# 1_CORE_schdoc.net
KiCad netlist of a schematic drawn in Altium Designer
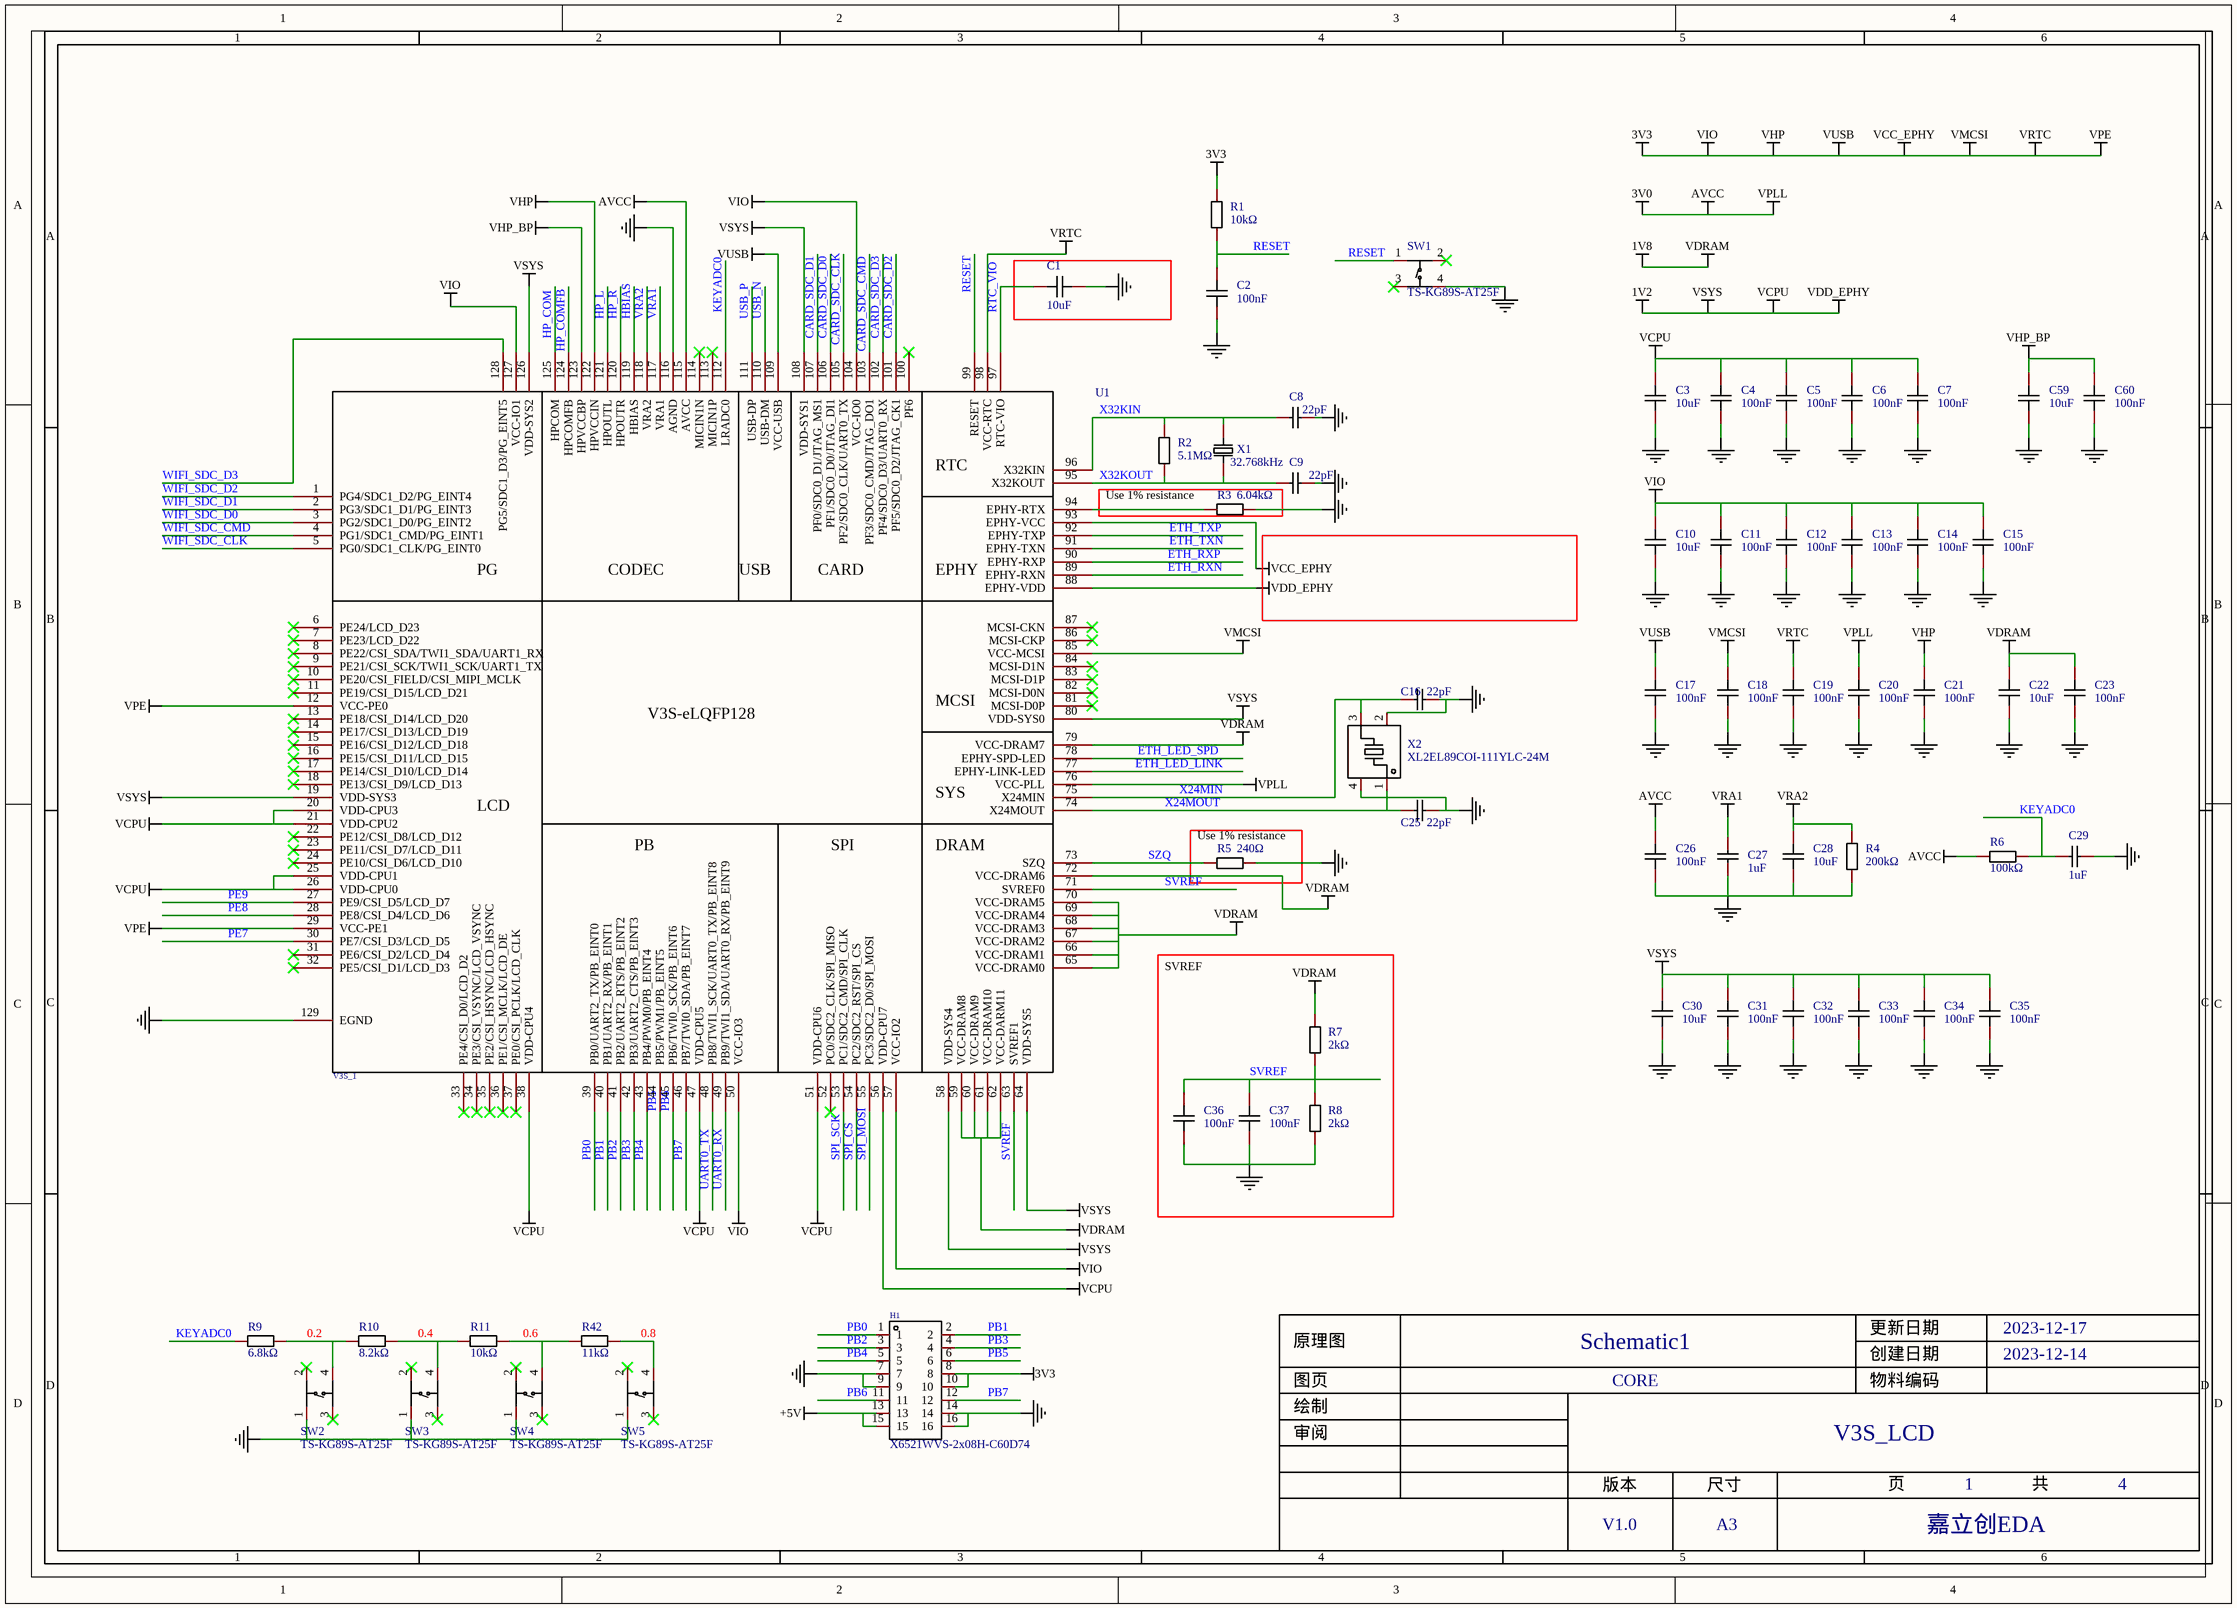
[diagram p0: 1_CORE.schdoc.schdoc]

(export (version "E")
  (design (tool "Eeschema 10.0.6"))
  (components
    (comp (ref "C1")
      (value "10uF")
      (fields
        (field (name "NAME") "10uF")
        (field (name "MANUFACTURER") "SAMSUNG(三星)")
        (field (name "MANUFACTURER PART") "CL10A106KP8NNNC")
        (field (name "TOLERANCE") "±10%")
      )
      (libsource (lib "altium-import") (part "root_0_CL10A106KP8NNNC_"))
    )
    (comp (ref "C2")
      (value "100nF")
      (fields
        (field (name "NAME") "100nF")
        (field (name "MANUFACTURER") "YAGEO(国巨)")
        (field (name "MANUFACTURER PART") "CC0603KRX7R9BB104")
        (field (name "TOLERANCE") "±10%")
      )
      (libsource (lib "altium-import") (part "root_1_CC0603KRX7R9BB104_"))
    )
    (comp (ref "C3")
      (value "10uF")
      (fields
        (field (name "NAME") "10uF")
        (field (name "MANUFACTURER") "SAMSUNG(三星)")
        (field (name "MANUFACTURER PART") "CL10A106KP8NNNC")
        (field (name "TOLERANCE") "±10%")
      )
      (libsource (lib "altium-import") (part "root_1_CL10A106KP8NNNC_"))
    )
    (comp (ref "C4")
      (value "100nF")
      (fields
        (field (name "NAME") "100nF")
        (field (name "MANUFACTURER") "YAGEO(国巨)")
        (field (name "MANUFACTURER PART") "CC0603KRX7R9BB104")
        (field (name "TOLERANCE") "±10%")
      )
      (libsource (lib "altium-import") (part "root_1_CC0603KRX7R9BB104_"))
    )
    (comp (ref "C5")
      (value "100nF")
      (fields
        (field (name "NAME") "100nF")
        (field (name "MANUFACTURER") "YAGEO(国巨)")
        (field (name "MANUFACTURER PART") "CC0603KRX7R9BB104")
        (field (name "TOLERANCE") "±10%")
      )
      (libsource (lib "altium-import") (part "root_1_CC0603KRX7R9BB104_"))
    )
    (comp (ref "C6")
      (value "100nF")
      (fields
        (field (name "NAME") "100nF")
        (field (name "MANUFACTURER") "YAGEO(国巨)")
        (field (name "MANUFACTURER PART") "CC0603KRX7R9BB104")
        (field (name "TOLERANCE") "±10%")
      )
      (libsource (lib "altium-import") (part "root_1_CC0603KRX7R9BB104_"))
    )
    (comp (ref "C7")
      (value "100nF")
      (fields
        (field (name "NAME") "100nF")
        (field (name "MANUFACTURER") "YAGEO(国巨)")
        (field (name "MANUFACTURER PART") "CC0603KRX7R9BB104")
        (field (name "TOLERANCE") "±10%")
      )
      (libsource (lib "altium-import") (part "root_1_CC0603KRX7R9BB104_"))
    )
    (comp (ref "C8")
      (value "22pF")
      (fields
        (field (name "NAME") "22pF")
        (field (name "MANUFACTURER PART") "CL10C220JB8NNNC")
        (field (name "MANUFACTURER") "SAMSUNG(三星)")
        (field (name "TOLERANCE") "±5%")
      )
      (libsource (lib "altium-import") (part "root_2_CL10C220JB8NNNC_"))
    )
    (comp (ref "C9")
      (value "22pF")
      (fields
        (field (name "NAME") "22pF")
        (field (name "MANUFACTURER PART") "CL10C220JB8NNNC")
        (field (name "MANUFACTURER") "SAMSUNG(三星)")
        (field (name "TOLERANCE") "±5%")
      )
      (libsource (lib "altium-import") (part "root_2_CL10C220JB8NNNC_"))
    )
    (comp (ref "C10")
      (value "10uF")
      (fields
        (field (name "NAME") "10uF")
        (field (name "MANUFACTURER") "SAMSUNG(三星)")
        (field (name "MANUFACTURER PART") "CL10A106KP8NNNC")
        (field (name "TOLERANCE") "±10%")
      )
      (libsource (lib "altium-import") (part "root_1_CL10A106KP8NNNC_"))
    )
    (comp (ref "C11")
      (value "100nF")
      (fields
        (field (name "NAME") "100nF")
        (field (name "MANUFACTURER") "YAGEO(国巨)")
        (field (name "MANUFACTURER PART") "CC0603KRX7R9BB104")
        (field (name "TOLERANCE") "±10%")
      )
      (libsource (lib "altium-import") (part "root_1_CC0603KRX7R9BB104_"))
    )
    (comp (ref "C12")
      (value "100nF")
      (fields
        (field (name "NAME") "100nF")
        (field (name "MANUFACTURER") "YAGEO(国巨)")
        (field (name "MANUFACTURER PART") "CC0603KRX7R9BB104")
        (field (name "TOLERANCE") "±10%")
      )
      (libsource (lib "altium-import") (part "root_1_CC0603KRX7R9BB104_"))
    )
    (comp (ref "C13")
      (value "100nF")
      (fields
        (field (name "NAME") "100nF")
        (field (name "MANUFACTURER") "YAGEO(国巨)")
        (field (name "MANUFACTURER PART") "CC0603KRX7R9BB104")
        (field (name "TOLERANCE") "±10%")
      )
      (libsource (lib "altium-import") (part "root_1_CC0603KRX7R9BB104_"))
    )
    (comp (ref "C14")
      (value "100nF")
      (fields
        (field (name "NAME") "100nF")
        (field (name "MANUFACTURER") "YAGEO(国巨)")
        (field (name "MANUFACTURER PART") "CC0603KRX7R9BB104")
        (field (name "TOLERANCE") "±10%")
      )
      (libsource (lib "altium-import") (part "root_1_CC0603KRX7R9BB104_"))
    )
    (comp (ref "C15")
      (value "100nF")
      (fields
        (field (name "NAME") "100nF")
        (field (name "MANUFACTURER") "YAGEO(国巨)")
        (field (name "MANUFACTURER PART") "CC0603KRX7R9BB104")
        (field (name "TOLERANCE") "±10%")
      )
      (libsource (lib "altium-import") (part "root_1_CC0603KRX7R9BB104_"))
    )
    (comp (ref "C16")
      (value "22pF")
      (fields
        (field (name "NAME") "22pF")
        (field (name "MANUFACTURER PART") "CL10C220JB8NNNC")
        (field (name "MANUFACTURER") "SAMSUNG(三星)")
        (field (name "TOLERANCE") "±5%")
      )
      (libsource (lib "altium-import") (part "root_0_CL10C220JB8NNNC_"))
    )
    (comp (ref "C17")
      (value "100nF")
      (fields
        (field (name "NAME") "100nF")
        (field (name "MANUFACTURER") "YAGEO(国巨)")
        (field (name "MANUFACTURER PART") "CC0603KRX7R9BB104")
        (field (name "TOLERANCE") "±10%")
      )
      (libsource (lib "altium-import") (part "root_1_CC0603KRX7R9BB104_"))
    )
    (comp (ref "C18")
      (value "100nF")
      (fields
        (field (name "NAME") "100nF")
        (field (name "MANUFACTURER") "YAGEO(国巨)")
        (field (name "MANUFACTURER PART") "CC0603KRX7R9BB104")
        (field (name "TOLERANCE") "±10%")
      )
      (libsource (lib "altium-import") (part "root_1_CC0603KRX7R9BB104_"))
    )
    (comp (ref "C19")
      (value "100nF")
      (fields
        (field (name "NAME") "100nF")
        (field (name "MANUFACTURER") "YAGEO(国巨)")
        (field (name "MANUFACTURER PART") "CC0603KRX7R9BB104")
        (field (name "TOLERANCE") "±10%")
      )
      (libsource (lib "altium-import") (part "root_1_CC0603KRX7R9BB104_"))
    )
    (comp (ref "C20")
      (value "100nF")
      (fields
        (field (name "NAME") "100nF")
        (field (name "MANUFACTURER") "YAGEO(国巨)")
        (field (name "MANUFACTURER PART") "CC0603KRX7R9BB104")
        (field (name "TOLERANCE") "±10%")
      )
      (libsource (lib "altium-import") (part "root_1_CC0603KRX7R9BB104_"))
    )
    (comp (ref "C21")
      (value "100nF")
      (fields
        (field (name "NAME") "100nF")
        (field (name "MANUFACTURER") "YAGEO(国巨)")
        (field (name "MANUFACTURER PART") "CC0603KRX7R9BB104")
        (field (name "TOLERANCE") "±10%")
      )
      (libsource (lib "altium-import") (part "root_1_CC0603KRX7R9BB104_"))
    )
    (comp (ref "C22")
      (value "10uF")
      (fields
        (field (name "NAME") "10uF")
        (field (name "MANUFACTURER") "SAMSUNG(三星)")
        (field (name "MANUFACTURER PART") "CL10A106KP8NNNC")
        (field (name "TOLERANCE") "±10%")
      )
      (libsource (lib "altium-import") (part "root_1_CL10A106KP8NNNC_"))
    )
    (comp (ref "C23")
      (value "100nF")
      (fields
        (field (name "NAME") "100nF")
        (field (name "MANUFACTURER") "YAGEO(国巨)")
        (field (name "MANUFACTURER PART") "CC0603KRX7R9BB104")
        (field (name "TOLERANCE") "±10%")
      )
      (libsource (lib "altium-import") (part "root_1_CC0603KRX7R9BB104_"))
    )
    (comp (ref "C25")
      (value "22pF")
      (fields
        (field (name "NAME") "22pF")
        (field (name "MANUFACTURER PART") "CL10C220JB8NNNC")
        (field (name "MANUFACTURER") "SAMSUNG(三星)")
        (field (name "TOLERANCE") "±5%")
      )
      (libsource (lib "altium-import") (part "root_0_CL10C220JB8NNNC_"))
    )
    (comp (ref "C26")
      (value "100nF")
      (fields
        (field (name "NAME") "100nF")
        (field (name "MANUFACTURER") "YAGEO(国巨)")
        (field (name "MANUFACTURER PART") "CC0603KRX7R9BB104")
        (field (name "TOLERANCE") "±10%")
      )
      (libsource (lib "altium-import") (part "root_1_CC0603KRX7R9BB104_"))
    )
    (comp (ref "C27")
      (value "1uF")
      (fields
        (field (name "NAME") "1uF")
        (field (name "MANUFACTURER PART") "CL10A105KB8NNNC")
        (field (name "MANUFACTURER") "SAMSUNG(三星)")
        (field (name "TOLERANCE") "±10%")
      )
      (libsource (lib "altium-import") (part "root_1_CL10A105KB8NNNC_"))
    )
    (comp (ref "C28")
      (value "10uF")
      (fields
        (field (name "NAME") "10uF")
        (field (name "MANUFACTURER") "SAMSUNG(三星)")
        (field (name "MANUFACTURER PART") "CL10A106KP8NNNC")
        (field (name "TOLERANCE") "±10%")
      )
      (libsource (lib "altium-import") (part "root_1_CL10A106KP8NNNC_"))
    )
    (comp (ref "C29")
      (value "1uF")
      (fields
        (field (name "NAME") "1uF")
        (field (name "MANUFACTURER PART") "CL10A105KB8NNNC")
        (field (name "MANUFACTURER") "SAMSUNG(三星)")
        (field (name "TOLERANCE") "±10%")
      )
      (libsource (lib "altium-import") (part "root_0_CL10A105KB8NNNC_"))
    )
    (comp (ref "C30")
      (value "10uF")
      (fields
        (field (name "NAME") "10uF")
        (field (name "MANUFACTURER") "SAMSUNG(三星)")
        (field (name "MANUFACTURER PART") "CL10A106KP8NNNC")
        (field (name "TOLERANCE") "±10%")
      )
      (libsource (lib "altium-import") (part "root_1_CL10A106KP8NNNC_"))
    )
    (comp (ref "C31")
      (value "100nF")
      (fields
        (field (name "NAME") "100nF")
        (field (name "MANUFACTURER") "YAGEO(国巨)")
        (field (name "MANUFACTURER PART") "CC0603KRX7R9BB104")
        (field (name "TOLERANCE") "±10%")
      )
      (libsource (lib "altium-import") (part "root_1_CC0603KRX7R9BB104_"))
    )
    (comp (ref "C32")
      (value "100nF")
      (fields
        (field (name "NAME") "100nF")
        (field (name "MANUFACTURER") "YAGEO(国巨)")
        (field (name "MANUFACTURER PART") "CC0603KRX7R9BB104")
        (field (name "TOLERANCE") "±10%")
      )
      (libsource (lib "altium-import") (part "root_1_CC0603KRX7R9BB104_"))
    )
    (comp (ref "C33")
      (value "100nF")
      (fields
        (field (name "NAME") "100nF")
        (field (name "MANUFACTURER") "YAGEO(国巨)")
        (field (name "MANUFACTURER PART") "CC0603KRX7R9BB104")
        (field (name "TOLERANCE") "±10%")
      )
      (libsource (lib "altium-import") (part "root_1_CC0603KRX7R9BB104_"))
    )
    (comp (ref "C34")
      (value "100nF")
      (fields
        (field (name "NAME") "100nF")
        (field (name "MANUFACTURER") "YAGEO(国巨)")
        (field (name "MANUFACTURER PART") "CC0603KRX7R9BB104")
        (field (name "TOLERANCE") "±10%")
      )
      (libsource (lib "altium-import") (part "root_1_CC0603KRX7R9BB104_"))
    )
    (comp (ref "C35")
      (value "100nF")
      (fields
        (field (name "NAME") "100nF")
        (field (name "MANUFACTURER") "YAGEO(国巨)")
        (field (name "MANUFACTURER PART") "CC0603KRX7R9BB104")
        (field (name "TOLERANCE") "±10%")
      )
      (libsource (lib "altium-import") (part "root_1_CC0603KRX7R9BB104_"))
    )
    (comp (ref "C36")
      (value "100nF")
      (fields
        (field (name "NAME") "100nF")
        (field (name "MANUFACTURER") "YAGEO(国巨)")
        (field (name "MANUFACTURER PART") "CC0603KRX7R9BB104")
        (field (name "TOLERANCE") "±10%")
      )
      (libsource (lib "altium-import") (part "root_1_CC0603KRX7R9BB104_"))
    )
    (comp (ref "C37")
      (value "100nF")
      (fields
        (field (name "NAME") "100nF")
        (field (name "MANUFACTURER") "YAGEO(国巨)")
        (field (name "MANUFACTURER PART") "CC0603KRX7R9BB104")
        (field (name "TOLERANCE") "±10%")
      )
      (libsource (lib "altium-import") (part "root_1_CC0603KRX7R9BB104_"))
    )
    (comp (ref "C59")
      (value "10uF")
      (fields
        (field (name "NAME") "10uF")
        (field (name "MANUFACTURER") "SAMSUNG(三星)")
        (field (name "MANUFACTURER PART") "CL10A106KP8NNNC")
        (field (name "TOLERANCE") "±10%")
      )
      (libsource (lib "altium-import") (part "root_1_CL10A106KP8NNNC_"))
    )
    (comp (ref "C60")
      (value "100nF")
      (fields
        (field (name "NAME") "100nF")
        (field (name "MANUFACTURER") "YAGEO(国巨)")
        (field (name "MANUFACTURER PART") "CC0603KRX7R9BB104")
        (field (name "TOLERANCE") "±10%")
      )
      (libsource (lib "altium-import") (part "root_1_CC0603KRX7R9BB104_"))
    )
    (comp (ref "H1")
      (value "X6521WVS-2x08H-C60D74")
      (fields
        (field (name "NAME") "X6521WVS-2x08H-C60D74")
        (field (name "MANUFACTURER") "XKB Connectivity(中国星坤)")
      )
      (libsource (lib "altium-import") (part "root_0_X6521WVS-2x08H-C60D74_"))
    )
    (comp (ref "R1")
      (value "10kΩ")
      (fields
        (field (name "NAME") "10kΩ")
        (field (name "MANUFACTURER") "UNI-ROYAL(厚声)")
        (field (name "MANUFACTURER PART") "0603WAF1002T5E")
        (field (name "TOLERANCE") "±1%")
      )
      (libsource (lib "altium-import") (part "root_1_0603WAF1002T5E_"))
    )
    (comp (ref "R2")
      (value "5.1MΩ")
      (fields
        (field (name "NAME") "5.1MΩ")
        (field (name "MANUFACTURER") "UNI-ROYAL(厚声)")
        (field (name "MANUFACTURER PART") "0603WAF5104T5E")
        (field (name "TOLERANCE") "±1%")
      )
      (libsource (lib "altium-import") (part "root_1_0603WAF5104T5E_"))
    )
    (comp (ref "R3")
      (value "6.04kΩ")
      (fields
        (field (name "NAME") "6.04kΩ")
        (field (name "MANUFACTURER") "FH(风华)")
        (field (name "MANUFACTURER PART") "RS-03K6041FT")
        (field (name "TOLERANCE") "±1%")
      )
      (libsource (lib "altium-import") (part "root_0_RS-03K6041FT_"))
    )
    (comp (ref "R4")
      (value "200kΩ")
      (fields
        (field (name "NAME") "200kΩ")
        (field (name "MANUFACTURER") "UNI-ROYAL(厚声)")
        (field (name "MANUFACTURER PART") "0603WAF2003T5E")
        (field (name "TOLERANCE") "±1%")
      )
      (libsource (lib "altium-import") (part "root_1_0603WAF2003T5E_"))
    )
    (comp (ref "R5")
      (value "240Ω")
      (fields
        (field (name "NAME") "240Ω")
        (field (name "MANUFACTURER") "UNI-ROYAL(厚声)")
        (field (name "MANUFACTURER PART") "0603WAF2400T5E")
        (field (name "TOLERANCE") "±1%")
      )
      (libsource (lib "altium-import") (part "root_0_0603WAF2400T5E_"))
    )
    (comp (ref "R6")
      (value "100kΩ")
      (fields
        (field (name "NAME") "100kΩ")
        (field (name "MANUFACTURER") "UNI-ROYAL(厚声)")
        (field (name "MANUFACTURER PART") "0603WAF1003T5E")
        (field (name "TOLERANCE") "±1%")
      )
      (libsource (lib "altium-import") (part "root_0_0603WAF1003T5E_"))
    )
    (comp (ref "R7")
      (value "2kΩ")
      (fields
        (field (name "NAME") "2kΩ")
        (field (name "MANUFACTURER") "UNI-ROYAL(厚声)")
        (field (name "MANUFACTURER PART") "0603WAF2001T5E")
        (field (name "TOLERANCE") "±1%")
      )
      (libsource (lib "altium-import") (part "root_1_0603WAF2001T5E_"))
    )
    (comp (ref "R8")
      (value "2kΩ")
      (fields
        (field (name "NAME") "2kΩ")
        (field (name "MANUFACTURER") "UNI-ROYAL(厚声)")
        (field (name "MANUFACTURER PART") "0603WAF2001T5E")
        (field (name "TOLERANCE") "±1%")
      )
      (libsource (lib "altium-import") (part "root_1_0603WAF2001T5E_"))
    )
    (comp (ref "R9")
      (value "6.8kΩ")
      (fields
        (field (name "NAME") "6.8kΩ")
        (field (name "MANUFACTURER") "UNI-ROYAL(厚声)")
        (field (name "MANUFACTURER PART") "0603WAF6801T5E")
        (field (name "TOLERANCE") "±1%")
      )
      (libsource (lib "altium-import") (part "root_0_0603WAF6801T5E_"))
    )
    (comp (ref "R10")
      (value "8.2kΩ")
      (fields
        (field (name "NAME") "8.2kΩ")
        (field (name "MANUFACTURER") "UNI-ROYAL(厚声)")
        (field (name "MANUFACTURER PART") "0603WAF8201T5E")
        (field (name "TOLERANCE") "±1%")
      )
      (libsource (lib "altium-import") (part "root_0_0603WAF8201T5E_"))
    )
    (comp (ref "R11")
      (value "10kΩ")
      (fields
        (field (name "NAME") "10kΩ")
        (field (name "MANUFACTURER") "UNI-ROYAL(厚声)")
        (field (name "MANUFACTURER PART") "0603WAF1002T5E")
        (field (name "TOLERANCE") "±1%")
      )
      (libsource (lib "altium-import") (part "root_0_0603WAF1002T5E_"))
    )
    (comp (ref "R42")
      (value "11kΩ")
      (fields
        (field (name "NAME") "11kΩ")
        (field (name "MANUFACTURER") "UNI-ROYAL(厚声)")
        (field (name "MANUFACTURER PART") "0603WAF1102T5E")
        (field (name "TOLERANCE") "±1%")
      )
      (libsource (lib "altium-import") (part "root_0_0603WAF1102T5E_"))
    )
    (comp (ref "SW1")
      (value "TS-KG89S-AT25F")
      (description "触点电流:50mA;额定电压(DC):12V;绝缘电阻:100MΩ;电路结构:单刀单掷;安装方式:立贴;作用力:250gf@±50gf;机械寿命:10万次;带支架:否;")
      (fields (field (name "NAME") "TS-KG89S-AT25F") (field (name "MANUFACTURER") "HANBO(汉博)"))
      (libsource (lib "altium-import") (part "root_0_TS-KG89S-AT25F_"))
    )
    (comp (ref "SW2")
      (value "TS-KG89S-AT25F")
      (description "触点电流:50mA;额定电压(DC):12V;绝缘电阻:100MΩ;电路结构:单刀单掷;安装方式:立贴;作用力:250gf@±50gf;机械寿命:10万次;带支架:否;")
      (fields (field (name "NAME") "TS-KG89S-AT25F") (field (name "MANUFACTURER") "HANBO(汉博)"))
      (libsource (lib "altium-import") (part "root_1_TS-KG89S-AT25F_"))
    )
    (comp (ref "SW3")
      (value "TS-KG89S-AT25F")
      (description "触点电流:50mA;额定电压(DC):12V;绝缘电阻:100MΩ;电路结构:单刀单掷;安装方式:立贴;作用力:250gf@±50gf;机械寿命:10万次;带支架:否;")
      (fields (field (name "NAME") "TS-KG89S-AT25F") (field (name "MANUFACTURER") "HANBO(汉博)"))
      (libsource (lib "altium-import") (part "root_1_TS-KG89S-AT25F_"))
    )
    (comp (ref "SW4")
      (value "TS-KG89S-AT25F")
      (description "触点电流:50mA;额定电压(DC):12V;绝缘电阻:100MΩ;电路结构:单刀单掷;安装方式:立贴;作用力:250gf@±50gf;机械寿命:10万次;带支架:否;")
      (fields (field (name "NAME") "TS-KG89S-AT25F") (field (name "MANUFACTURER") "HANBO(汉博)"))
      (libsource (lib "altium-import") (part "root_1_TS-KG89S-AT25F_"))
    )
    (comp (ref "SW5")
      (value "TS-KG89S-AT25F")
      (description "触点电流:50mA;额定电压(DC):12V;绝缘电阻:100MΩ;电路结构:单刀单掷;安装方式:立贴;作用力:250gf@±50gf;机械寿命:10万次;带支架:否;")
      (fields (field (name "NAME") "TS-KG89S-AT25F") (field (name "MANUFACTURER") "HANBO(汉博)"))
      (libsource (lib "altium-import") (part "root_1_TS-KG89S-AT25F_"))
    )
    (comp (ref "U1")
      (value "V3S_1")
      (fields (field (name "NAME") "V3S_1"))
      (libsource (lib "altium-import") (part "root_0_LQFP129 14x14_N_"))
    )
    (comp (ref "X1")
      (value "32.768kHz")
      (description "频率:32.768kHz;负载电容:12.5pF;频率公差:±20ppm;")
      (fields
        (field (name "NAME") "32.768kHz")
        (field (name "MANUFACTURER PART") "Q13FC1350000400")
        (field (name "MANUFACTURER") "EPSON(爱普生)")
      )
      (libsource (lib "altium-import") (part "root_1_Q13FC1350000400_"))
    )
    (comp (ref "X2")
      (value "XL2EL89COI-111YLC-24M")
      (description "频率： 24MHZ 负载： 12PF 频率公差： ±10PPM 工作温度： -40~85℃")
      (fields (field (name "NAME") "XL2EL89COI-111YLC-24M") (field (name "MANUFACTURER") "YXC(扬兴晶振)"))
      (libsource (lib "altium-import") (part "root_1_XL2EL89COI-111YLC-24M_"))
    )
  )
  (nets
    (net (code "1") (name "+5V") (class "Default")
      (node (ref "H1") (pin "13") (pinfunction "13_13") (pintype "passive"))
      (node (ref "H1") (pin "15") (pinfunction "15_15") (pintype "passive"))
    )
    (net (code "2") (name "/CARD_SDC_CLK") (class "Default")
      (node (ref "U1") (pin "105") (pinfunction "PF2/SDC0_CLK/UART0_TX_105") (pintype "passive"))
    )
    (net (code "3") (name "/CARD_SDC_CMD") (class "Default")
      (node (ref "U1") (pin "103") (pinfunction "PF3/SDC0_CMD/JTAG_DO1_103") (pintype "passive"))
    )
    (net (code "4") (name "/CARD_SDC_D0") (class "Default")
      (node (ref "U1") (pin "106") (pinfunction "PF1/SDC0_D0/JTAG_DI1_106") (pintype "passive"))
    )
    (net (code "5") (name "/CARD_SDC_D1") (class "Default")
      (node (ref "U1") (pin "107") (pinfunction "PF0/SDC0_D1/JTAG_MS1_107") (pintype "passive"))
    )
    (net (code "6") (name "/CARD_SDC_D2") (class "Default")
      (node (ref "U1") (pin "101") (pinfunction "PF5/SDC0_D2/JTAG_CK1_101") (pintype "passive"))
    )
    (net (code "7") (name "/CARD_SDC_D3") (class "Default")
      (node (ref "U1") (pin "102") (pinfunction "PF4/SDC0_D3/UART0_RX_102") (pintype "passive"))
    )
    (net (code "8") (name "/ETH_LED_LINK") (class "Default")
      (node (ref "U1") (pin "77") (pinfunction "EPHY-LINK-LED_77") (pintype "passive"))
    )
    (net (code "9") (name "/ETH_LED_SPD") (class "Default")
      (node (ref "U1") (pin "78") (pinfunction "EPHY-SPD-LED_78") (pintype "passive"))
    )
    (net (code "10") (name "/ETH_RXN") (class "Default")
      (node (ref "U1") (pin "89") (pinfunction "EPHY-RXN_89") (pintype "passive"))
    )
    (net (code "11") (name "/ETH_RXP") (class "Default")
      (node (ref "U1") (pin "90") (pinfunction "EPHY-RXP_90") (pintype "passive"))
    )
    (net (code "12") (name "/ETH_TXN") (class "Default")
      (node (ref "U1") (pin "91") (pinfunction "EPHY-TXN_91") (pintype "passive"))
    )
    (net (code "13") (name "/ETH_TXP") (class "Default")
      (node (ref "U1") (pin "92") (pinfunction "EPHY-TXP_92") (pintype "passive"))
    )
    (net (code "14") (name "/HBIAS") (class "Default")
      (node (ref "U1") (pin "119") (pinfunction "HBIAS_119") (pintype "passive"))
    )
    (net (code "15") (name "/HP_COM") (class "Default")
      (node (ref "U1") (pin "125") (pinfunction "HPCOM_125") (pintype "passive"))
    )
    (net (code "16") (name "/HP_COMFB") (class "Default")
      (node (ref "U1") (pin "124") (pinfunction "HPCOMFB_124") (pintype "passive"))
    )
    (net (code "17") (name "/HP_L") (class "Default")
      (node (ref "U1") (pin "121") (pinfunction "HPOUTL_121") (pintype "passive"))
    )
    (net (code "18") (name "/HP_R") (class "Default")
      (node (ref "U1") (pin "120") (pinfunction "HPOUTR_120") (pintype "passive"))
    )
    (net (code "19") (name "/KEYADC0") (class "Default")
      (node (ref "C29") (pin "1") (pinfunction "1_1") (pintype "passive"))
      (node (ref "R6") (pin "2") (pinfunction "2_2") (pintype "passive"))
      (node (ref "R9") (pin "1") (pinfunction "1_1") (pintype "passive"))
      (node (ref "U1") (pin "112") (pinfunction "LRADC0_112") (pintype "passive"))
    )
    (net (code "20") (name "/PB0") (class "Default")
      (node (ref "H1") (pin "1") (pinfunction "1_1") (pintype "passive"))
      (node (ref "U1") (pin "39") (pinfunction "PB0/UART2_TX/PB_EINT0_39") (pintype "passive"))
    )
    (net (code "21") (name "/PB1") (class "Default")
      (node (ref "H1") (pin "2") (pinfunction "2_2") (pintype "passive"))
      (node (ref "U1") (pin "40") (pinfunction "PB1/UART2_RX/PB_EINT1_40") (pintype "passive"))
    )
    (net (code "22") (name "/PB2") (class "Default")
      (node (ref "H1") (pin "3") (pinfunction "3_3") (pintype "passive"))
      (node (ref "U1") (pin "41") (pinfunction "PB2/UART2_RTS/PB_EINT2_41") (pintype "passive"))
    )
    (net (code "23") (name "/PB3") (class "Default")
      (node (ref "H1") (pin "4") (pinfunction "4_4") (pintype "passive"))
      (node (ref "U1") (pin "42") (pinfunction "PB3/UART2_CTS/PB_EINT3_42") (pintype "passive"))
    )
    (net (code "24") (name "/PB4") (class "Default")
      (node (ref "H1") (pin "5") (pinfunction "5_5") (pintype "passive"))
      (node (ref "U1") (pin "43") (pinfunction "PB4/PWM0/PB_EINT4_43") (pintype "passive"))
    )
    (net (code "25") (name "/PB5") (class "Default")
      (node (ref "H1") (pin "6") (pinfunction "6_6") (pintype "passive"))
      (node (ref "U1") (pin "44") (pinfunction "PB5/PWM1/PB_EINT5_44") (pintype "passive"))
    )
    (net (code "26") (name "/PB6") (class "Default")
      (node (ref "H1") (pin "11") (pinfunction "11_11") (pintype "passive"))
      (node (ref "U1") (pin "45") (pinfunction "PB6/TWI0_SCK/PB_EINT6_45") (pintype "passive"))
    )
    (net (code "27") (name "/PB7") (class "Default")
      (node (ref "H1") (pin "12") (pinfunction "12_12") (pintype "passive"))
      (node (ref "U1") (pin "46") (pinfunction "PB7/TWI0_SDA/PB_EINT7_46") (pintype "passive"))
    )
    (net (code "28") (name "/PE7") (class "Default")
      (node (ref "U1") (pin "30") (pinfunction "PE7/CSI_D3/LCD_D5_30") (pintype "passive"))
    )
    (net (code "29") (name "/PE8") (class "Default")
      (node (ref "U1") (pin "28") (pinfunction "PE8/CSI_D4/LCD_D6_28") (pintype "passive"))
    )
    (net (code "30") (name "/PE9") (class "Default")
      (node (ref "U1") (pin "27") (pinfunction "PE9/CSI_D5/LCD_D7_27") (pintype "passive"))
    )
    (net (code "31") (name "/RESET") (class "Default")
      (node (ref "C2") (pin "2") (pinfunction "2_2") (pintype "passive"))
      (node (ref "R1") (pin "1") (pinfunction "1_1") (pintype "passive"))
      (node (ref "SW1") (pin "1") (pinfunction "1_1") (pintype "passive"))
      (node (ref "U1") (pin "99") (pinfunction "RESET_99") (pintype "passive"))
    )
    (net (code "32") (name "/RTC_VIO") (class "Default")
      (node (ref "C1") (pin "1") (pinfunction "1_1") (pintype "passive"))
      (node (ref "U1") (pin "97") (pinfunction "RTC-VIO_97") (pintype "passive"))
    )
    (net (code "33") (name "/SPI_CS") (class "Default")
      (node (ref "U1") (pin "54") (pinfunction "PC2/SDC2_RST/SPI_CS_54") (pintype "passive"))
    )
    (net (code "34") (name "/SPI_MOSI") (class "Default")
      (node (ref "U1") (pin "55") (pinfunction "PC3/SDC2_D0/SPI_MOSI_55") (pintype "passive"))
    )
    (net (code "35") (name "/SPI_SCK") (class "Default")
      (node (ref "U1") (pin "53") (pinfunction "PC1/SDC2_CMD/SPI_CLK_53") (pintype "passive"))
    )
    (net (code "36") (name "/SVREF") (class "Default")
      (node (ref "C36") (pin "2") (pinfunction "2_2") (pintype "passive"))
      (node (ref "C37") (pin "2") (pinfunction "2_2") (pintype "passive"))
      (node (ref "R7") (pin "1") (pinfunction "1_1") (pintype "passive"))
      (node (ref "R8") (pin "2") (pinfunction "2_2") (pintype "passive"))
      (node (ref "U1") (pin "63") (pinfunction "SVREF1_63") (pintype "passive"))
      (node (ref "U1") (pin "71") (pinfunction "SVREF0_71") (pintype "passive"))
    )
    (net (code "37") (name "/SZQ") (class "Default")
      (node (ref "R5") (pin "1") (pinfunction "1_1") (pintype "passive"))
      (node (ref "U1") (pin "73") (pinfunction "SZQ_73") (pintype "passive"))
    )
    (net (code "38") (name "/UART0_RX") (class "Default")
      (node (ref "U1") (pin "49") (pinfunction "PB9/TWI1_SDA/UART0_RX/PB_EINT9_49") (pintype "passive"))
    )
    (net (code "39") (name "/UART0_TX") (class "Default")
      (node (ref "U1") (pin "48") (pinfunction "PB8/TWI1_SCK/UART0_TX/PB_EINT8_48") (pintype "passive"))
    )
    (net (code "40") (name "/USB_N") (class "Default")
      (node (ref "U1") (pin "110") (pinfunction "USB-DM_110") (pintype "passive"))
    )
    (net (code "41") (name "/USB_P") (class "Default")
      (node (ref "U1") (pin "111") (pinfunction "USB-DP_111") (pintype "passive"))
    )
    (net (code "42") (name "/WIFI_SDC_CLK") (class "Default")
      (node (ref "U1") (pin "5") (pinfunction "PG0/SDC1_CLK/PG_EINT0_5") (pintype "passive"))
    )
    (net (code "43") (name "/WIFI_SDC_CMD") (class "Default")
      (node (ref "U1") (pin "4") (pinfunction "PG1/SDC1_CMD/PG_EINT1_4") (pintype "passive"))
    )
    (net (code "44") (name "/WIFI_SDC_D0") (class "Default")
      (node (ref "U1") (pin "3") (pinfunction "PG2/SDC1_D0/PG_EINT2_3") (pintype "passive"))
    )
    (net (code "45") (name "/WIFI_SDC_D1") (class "Default")
      (node (ref "U1") (pin "2") (pinfunction "PG3/SDC1_D1/PG_EINT3_2") (pintype "passive"))
    )
    (net (code "46") (name "/WIFI_SDC_D2") (class "Default")
      (node (ref "U1") (pin "1") (pinfunction "PG4/SDC1_D2/PG_EINT4_1") (pintype "passive"))
    )
    (net (code "47") (name "/WIFI_SDC_D3") (class "Default")
      (node (ref "U1") (pin "128") (pinfunction "PG5/SDC1_D3/PG_EINT5_128") (pintype "passive"))
    )
    (net (code "48") (name "/X24MIN") (class "Default")
      (node (ref "C16") (pin "1") (pinfunction "1_1") (pintype "passive"))
      (node (ref "U1") (pin "75") (pinfunction "X24MIN_75") (pintype "passive"))
      (node (ref "X2") (pin "3") (pinfunction "3_3") (pintype "passive"))
    )
    (net (code "49") (name "/X24MOUT") (class "Default")
      (node (ref "C25") (pin "1") (pinfunction "1_1") (pintype "passive"))
      (node (ref "U1") (pin "74") (pinfunction "X24MOUT_74") (pintype "passive"))
      (node (ref "X2") (pin "1") (pinfunction "1_1") (pintype "passive"))
    )
    (net (code "50") (name "/X32KIN") (class "Default")
      (node (ref "C8") (pin "2") (pinfunction "2_2") (pintype "passive"))
      (node (ref "R2") (pin "2") (pinfunction "2_2") (pintype "passive"))
      (node (ref "U1") (pin "96") (pinfunction "X32KIN_96") (pintype "passive"))
      (node (ref "X1") (pin "2") (pinfunction "2_2") (pintype "passive"))
    )
    (net (code "51") (name "/X32KOUT") (class "Default")
      (node (ref "C9") (pin "2") (pinfunction "2_2") (pintype "passive"))
      (node (ref "R2") (pin "1") (pinfunction "1_1") (pintype "passive"))
      (node (ref "U1") (pin "95") (pinfunction "X32KOUT_95") (pintype "passive"))
      (node (ref "X1") (pin "1") (pinfunction "1_1") (pintype "passive"))
    )
    (net (code "52") (name "1V2") (class "Default")
      (node (ref "C3") (pin "2") (pinfunction "2_2") (pintype "passive"))
      (node (ref "C30") (pin "2") (pinfunction "2_2") (pintype "passive"))
      (node (ref "C31") (pin "2") (pinfunction "2_2") (pintype "passive"))
      (node (ref "C32") (pin "2") (pinfunction "2_2") (pintype "passive"))
      (node (ref "C33") (pin "2") (pinfunction "2_2") (pintype "passive"))
      (node (ref "C34") (pin "2") (pinfunction "2_2") (pintype "passive"))
      (node (ref "C35") (pin "2") (pinfunction "2_2") (pintype "passive"))
      (node (ref "C4") (pin "2") (pinfunction "2_2") (pintype "passive"))
      (node (ref "C5") (pin "2") (pinfunction "2_2") (pintype "passive"))
      (node (ref "C6") (pin "2") (pinfunction "2_2") (pintype "passive"))
      (node (ref "C7") (pin "2") (pinfunction "2_2") (pintype "passive"))
      (node (ref "U1") (pin "108") (pinfunction "VDD-SYS1_108") (pintype "passive"))
      (node (ref "U1") (pin "126") (pinfunction "VDD-SYS2_126") (pintype "passive"))
      (node (ref "U1") (pin "19") (pinfunction "VDD-SYS3_19") (pintype "passive"))
      (node (ref "U1") (pin "20") (pinfunction "VDD-CPU3_20") (pintype "passive"))
      (node (ref "U1") (pin "21") (pinfunction "VDD-CPU2_21") (pintype "passive"))
      (node (ref "U1") (pin "25") (pinfunction "VDD-CPU1_25") (pintype "passive"))
      (node (ref "U1") (pin "26") (pinfunction "VDD-CPU0_26") (pintype "passive"))
      (node (ref "U1") (pin "38") (pinfunction "VDD-CPU4_38") (pintype "passive"))
      (node (ref "U1") (pin "47") (pinfunction "VDD-CPU5_47") (pintype "passive"))
      (node (ref "U1") (pin "51") (pinfunction "VDD-CPU6_51") (pintype "passive"))
      (node (ref "U1") (pin "56") (pinfunction "VDD-CPU7_56") (pintype "passive"))
      (node (ref "U1") (pin "58") (pinfunction "VDD-SYS4_58") (pintype "passive"))
      (node (ref "U1") (pin "64") (pinfunction "VDD-SYS5_64") (pintype "passive"))
      (node (ref "U1") (pin "80") (pinfunction "VDD-SYS0_80") (pintype "passive"))
      (node (ref "U1") (pin "88") (pinfunction "EPHY-VDD_88") (pintype "passive"))
    )
    (net (code "53") (name "1V8") (class "Default")
      (node (ref "C22") (pin "2") (pinfunction "2_2") (pintype "passive"))
      (node (ref "C23") (pin "2") (pinfunction "2_2") (pintype "passive"))
      (node (ref "R7") (pin "2") (pinfunction "2_2") (pintype "passive"))
      (node (ref "U1") (pin "59") (pinfunction "VCC-DRAM8_59") (pintype "passive"))
      (node (ref "U1") (pin "60") (pinfunction "VCC-DRAM9_60") (pintype "passive"))
      (node (ref "U1") (pin "61") (pinfunction "VCC-DRAM10_61") (pintype "passive"))
      (node (ref "U1") (pin "62") (pinfunction "VCC-DARM11_62") (pintype "passive"))
      (node (ref "U1") (pin "65") (pinfunction "VCC-DRAM0_65") (pintype "passive"))
      (node (ref "U1") (pin "66") (pinfunction "VCC-DRAM1_66") (pintype "passive"))
      (node (ref "U1") (pin "67") (pinfunction "VCC-DRAM2_67") (pintype "passive"))
      (node (ref "U1") (pin "68") (pinfunction "VCC-DRAM3_68") (pintype "passive"))
      (node (ref "U1") (pin "69") (pinfunction "VCC-DRAM4_69") (pintype "passive"))
      (node (ref "U1") (pin "70") (pinfunction "VCC-DRAM5_70") (pintype "passive"))
      (node (ref "U1") (pin "72") (pinfunction "VCC-DRAM6_72") (pintype "passive"))
      (node (ref "U1") (pin "79") (pinfunction "VCC-DRAM7_79") (pintype "passive"))
    )
    (net (code "54") (name "3V0") (class "Default")
      (node (ref "C20") (pin "2") (pinfunction "2_2") (pintype "passive"))
      (node (ref "C26") (pin "2") (pinfunction "2_2") (pintype "passive"))
      (node (ref "R6") (pin "1") (pinfunction "1_1") (pintype "passive"))
      (node (ref "U1") (pin "115") (pinfunction "AVCC_115") (pintype "passive"))
      (node (ref "U1") (pin "76") (pinfunction "VCC-PLL_76") (pintype "passive"))
    )
    (net (code "55") (name "3V3") (class "Default")
      (node (ref "C10") (pin "2") (pinfunction "2_2") (pintype "passive"))
      (node (ref "C11") (pin "2") (pinfunction "2_2") (pintype "passive"))
      (node (ref "C12") (pin "2") (pinfunction "2_2") (pintype "passive"))
      (node (ref "C13") (pin "2") (pinfunction "2_2") (pintype "passive"))
      (node (ref "C14") (pin "2") (pinfunction "2_2") (pintype "passive"))
      (node (ref "C15") (pin "2") (pinfunction "2_2") (pintype "passive"))
      (node (ref "C17") (pin "2") (pinfunction "2_2") (pintype "passive"))
      (node (ref "C18") (pin "2") (pinfunction "2_2") (pintype "passive"))
      (node (ref "C19") (pin "2") (pinfunction "2_2") (pintype "passive"))
      (node (ref "C21") (pin "2") (pinfunction "2_2") (pintype "passive"))
      (node (ref "H1") (pin "10") (pinfunction "10_10") (pintype "passive"))
      (node (ref "H1") (pin "8") (pinfunction "8_8") (pintype "passive"))
      (node (ref "R1") (pin "2") (pinfunction "2_2") (pintype "passive"))
      (node (ref "U1") (pin "104") (pinfunction "VCC-IO0_104") (pintype "passive"))
      (node (ref "U1") (pin "109") (pinfunction "VCC-USB_109") (pintype "passive"))
      (node (ref "U1") (pin "12") (pinfunction "VCC-PE0_12") (pintype "passive"))
      (node (ref "U1") (pin "122") (pinfunction "HPVCCIN_122") (pintype "passive"))
      (node (ref "U1") (pin "127") (pinfunction "VCC-IO1_127") (pintype "passive"))
      (node (ref "U1") (pin "29") (pinfunction "VCC-PE1_29") (pintype "passive"))
      (node (ref "U1") (pin "50") (pinfunction "VCC-IO3_50") (pintype "passive"))
      (node (ref "U1") (pin "57") (pinfunction "VCC-IO2_57") (pintype "passive"))
      (node (ref "U1") (pin "85") (pinfunction "VCC-MCSI_85") (pintype "passive"))
      (node (ref "U1") (pin "93") (pinfunction "EPHY-VCC_93") (pintype "passive"))
      (node (ref "U1") (pin "98") (pinfunction "VCC-RTC_98") (pintype "passive"))
    )
    (net (code "56") (name "<NO NET>") (class "Default")
      (node (ref "C1") (pin "2") (pinfunction "2_2") (pintype "passive"))
      (node (ref "C10") (pin "1") (pinfunction "1_1") (pintype "passive"))
      (node (ref "C11") (pin "1") (pinfunction "1_1") (pintype "passive"))
      (node (ref "C12") (pin "1") (pinfunction "1_1") (pintype "passive"))
      (node (ref "C13") (pin "1") (pinfunction "1_1") (pintype "passive"))
      (node (ref "C14") (pin "1") (pinfunction "1_1") (pintype "passive"))
      (node (ref "C15") (pin "1") (pinfunction "1_1") (pintype "passive"))
      (node (ref "C16") (pin "2") (pinfunction "2_2") (pintype "passive"))
      (node (ref "C17") (pin "1") (pinfunction "1_1") (pintype "passive"))
      (node (ref "C18") (pin "1") (pinfunction "1_1") (pintype "passive"))
      (node (ref "C19") (pin "1") (pinfunction "1_1") (pintype "passive"))
      (node (ref "C2") (pin "1") (pinfunction "1_1") (pintype "passive"))
      (node (ref "C20") (pin "1") (pinfunction "1_1") (pintype "passive"))
      (node (ref "C21") (pin "1") (pinfunction "1_1") (pintype "passive"))
      (node (ref "C22") (pin "1") (pinfunction "1_1") (pintype "passive"))
      (node (ref "C23") (pin "1") (pinfunction "1_1") (pintype "passive"))
      (node (ref "C25") (pin "2") (pinfunction "2_2") (pintype "passive"))
      (node (ref "C26") (pin "1") (pinfunction "1_1") (pintype "passive"))
      (node (ref "C27") (pin "1") (pinfunction "1_1") (pintype "passive"))
      (node (ref "C28") (pin "1") (pinfunction "1_1") (pintype "passive"))
      (node (ref "C29") (pin "2") (pinfunction "2_2") (pintype "passive"))
      (node (ref "C3") (pin "1") (pinfunction "1_1") (pintype "passive"))
      (node (ref "C30") (pin "1") (pinfunction "1_1") (pintype "passive"))
      (node (ref "C31") (pin "1") (pinfunction "1_1") (pintype "passive"))
      (node (ref "C32") (pin "1") (pinfunction "1_1") (pintype "passive"))
      (node (ref "C33") (pin "1") (pinfunction "1_1") (pintype "passive"))
      (node (ref "C34") (pin "1") (pinfunction "1_1") (pintype "passive"))
      (node (ref "C35") (pin "1") (pinfunction "1_1") (pintype "passive"))
      (node (ref "C36") (pin "1") (pinfunction "1_1") (pintype "passive"))
      (node (ref "C37") (pin "1") (pinfunction "1_1") (pintype "passive"))
      (node (ref "C4") (pin "1") (pinfunction "1_1") (pintype "passive"))
      (node (ref "C5") (pin "1") (pinfunction "1_1") (pintype "passive"))
      (node (ref "C59") (pin "1") (pinfunction "1_1") (pintype "passive"))
      (node (ref "C6") (pin "1") (pinfunction "1_1") (pintype "passive"))
      (node (ref "C60") (pin "1") (pinfunction "1_1") (pintype "passive"))
      (node (ref "C7") (pin "1") (pinfunction "1_1") (pintype "passive"))
      (node (ref "C8") (pin "1") (pinfunction "1_1") (pintype "passive"))
      (node (ref "C9") (pin "1") (pinfunction "1_1") (pintype "passive"))
      (node (ref "H1") (pin "14") (pinfunction "14_14") (pintype "passive"))
      (node (ref "H1") (pin "16") (pinfunction "16_16") (pintype "passive"))
      (node (ref "H1") (pin "7") (pinfunction "7_7") (pintype "passive"))
      (node (ref "H1") (pin "9") (pinfunction "9_9") (pintype "passive"))
      (node (ref "R3") (pin "2") (pinfunction "2_2") (pintype "passive"))
      (node (ref "R4") (pin "1") (pinfunction "1_1") (pintype "passive"))
      (node (ref "R5") (pin "2") (pinfunction "2_2") (pintype "passive"))
      (node (ref "R8") (pin "1") (pinfunction "1_1") (pintype "passive"))
      (node (ref "SW1") (pin "4") (pinfunction "4_4") (pintype "passive"))
      (node (ref "SW2") (pin "1") (pinfunction "1_1") (pintype "passive"))
      (node (ref "SW3") (pin "1") (pinfunction "1_1") (pintype "passive"))
      (node (ref "SW4") (pin "1") (pinfunction "1_1") (pintype "passive"))
      (node (ref "SW5") (pin "1") (pinfunction "1_1") (pintype "passive"))
      (node (ref "U1") (pin "116") (pinfunction "AGND_116") (pintype "passive"))
      (node (ref "U1") (pin "129") (pinfunction "EGND_129") (pintype "passive"))
      (node (ref "X2") (pin "2") (pinfunction "GND_2") (pintype "passive"))
      (node (ref "X2") (pin "4") (pinfunction "GND_4") (pintype "passive"))
    )
    (net (code "57") (name "Net-(R10-Pad1)") (class "Default")
      (node (ref "R10") (pin "1") (pinfunction "1_1") (pintype "passive"))
      (node (ref "R9") (pin "2") (pinfunction "2_2") (pintype "passive"))
      (node (ref "SW2") (pin "4") (pinfunction "4_4") (pintype "passive"))
    )
    (net (code "58") (name "Net-(R10-Pad2)") (class "Default")
      (node (ref "R10") (pin "2") (pinfunction "2_2") (pintype "passive"))
      (node (ref "R11") (pin "1") (pinfunction "1_1") (pintype "passive"))
      (node (ref "SW3") (pin "4") (pinfunction "4_4") (pintype "passive"))
    )
    (net (code "59") (name "Net-(R11-Pad2)") (class "Default")
      (node (ref "R11") (pin "2") (pinfunction "2_2") (pintype "passive"))
      (node (ref "R42") (pin "1") (pinfunction "1_1") (pintype "passive"))
      (node (ref "SW4") (pin "4") (pinfunction "4_4") (pintype "passive"))
    )
    (net (code "60") (name "Net-(R42-Pad2)") (class "Default")
      (node (ref "R42") (pin "2") (pinfunction "2_2") (pintype "passive"))
      (node (ref "SW5") (pin "4") (pinfunction "4_4") (pintype "passive"))
    )
    (net (code "61") (name "Net-(U1-EPHY-RTX)") (class "Default")
      (node (ref "R3") (pin "1") (pinfunction "1_1") (pintype "passive"))
      (node (ref "U1") (pin "94") (pinfunction "EPHY-RTX_94") (pintype "passive"))
    )
    (net (code "62") (name "VHP_BP") (class "Default")
      (node (ref "C59") (pin "2") (pinfunction "2_2") (pintype "passive"))
      (node (ref "C60") (pin "2") (pinfunction "2_2") (pintype "passive"))
      (node (ref "U1") (pin "123") (pinfunction "HPVCCBP_123") (pintype "passive"))
    )
    (net (code "63") (name "VRA1") (class "Default")
      (node (ref "C27") (pin "2") (pinfunction "2_2") (pintype "passive"))
      (node (ref "U1") (pin "117") (pinfunction "VRA1_117") (pintype "passive"))
    )
    (net (code "64") (name "VRA2") (class "Default")
      (node (ref "C28") (pin "2") (pinfunction "2_2") (pintype "passive"))
      (node (ref "R4") (pin "2") (pinfunction "2_2") (pintype "passive"))
      (node (ref "U1") (pin "118") (pinfunction "VRA2_118") (pintype "passive"))
    )
    (net (code "65") (name "unconnected-(SW1-Pad2)") (class "Default")
      (node (ref "SW1") (pin "2") (pinfunction "2_2") (pintype "passive+no_connect"))
    )
    (net (code "66") (name "unconnected-(SW1-Pad3)") (class "Default")
      (node (ref "SW1") (pin "3") (pinfunction "3_3") (pintype "passive+no_connect"))
    )
    (net (code "67") (name "unconnected-(SW2-Pad2)") (class "Default")
      (node (ref "SW2") (pin "2") (pinfunction "2_2") (pintype "passive+no_connect"))
    )
    (net (code "68") (name "unconnected-(SW2-Pad3)") (class "Default")
      (node (ref "SW2") (pin "3") (pinfunction "3_3") (pintype "passive+no_connect"))
    )
    (net (code "69") (name "unconnected-(SW3-Pad2)") (class "Default")
      (node (ref "SW3") (pin "2") (pinfunction "2_2") (pintype "passive+no_connect"))
    )
    (net (code "70") (name "unconnected-(SW3-Pad3)") (class "Default")
      (node (ref "SW3") (pin "3") (pinfunction "3_3") (pintype "passive+no_connect"))
    )
    (net (code "71") (name "unconnected-(SW4-Pad2)") (class "Default")
      (node (ref "SW4") (pin "2") (pinfunction "2_2") (pintype "passive+no_connect"))
    )
    (net (code "72") (name "unconnected-(SW4-Pad3)") (class "Default")
      (node (ref "SW4") (pin "3") (pinfunction "3_3") (pintype "passive+no_connect"))
    )
    (net (code "73") (name "unconnected-(SW5-Pad2)") (class "Default")
      (node (ref "SW5") (pin "2") (pinfunction "2_2") (pintype "passive+no_connect"))
    )
    (net (code "74") (name "unconnected-(SW5-Pad3)") (class "Default")
      (node (ref "SW5") (pin "3") (pinfunction "3_3") (pintype "passive+no_connect"))
    )
    (net (code "75") (name "unconnected-(U1-MCSI-CKN-Pad87)") (class "Default")
      (node (ref "U1") (pin "87") (pinfunction "MCSI-CKN_87") (pintype "passive+no_connect"))
    )
    (net (code "76") (name "unconnected-(U1-MCSI-CKP-Pad86)") (class "Default")
      (node (ref "U1") (pin "86") (pinfunction "MCSI-CKP_86") (pintype "passive+no_connect"))
    )
    (net (code "77") (name "unconnected-(U1-MCSI-D0N-Pad82)") (class "Default")
      (node (ref "U1") (pin "82") (pinfunction "MCSI-D0N_82") (pintype "passive+no_connect"))
    )
    (net (code "78") (name "unconnected-(U1-MCSI-D0P-Pad81)") (class "Default")
      (node (ref "U1") (pin "81") (pinfunction "MCSI-D0P_81") (pintype "passive+no_connect"))
    )
    (net (code "79") (name "unconnected-(U1-MCSI-D1N-Pad84)") (class "Default")
      (node (ref "U1") (pin "84") (pinfunction "MCSI-D1N_84") (pintype "passive+no_connect"))
    )
    (net (code "80") (name "unconnected-(U1-MCSI-D1P-Pad83)") (class "Default")
      (node (ref "U1") (pin "83") (pinfunction "MCSI-D1P_83") (pintype "passive+no_connect"))
    )
    (net (code "81") (name "unconnected-(U1-MICIN1N-Pad114)") (class "Default")
      (node (ref "U1") (pin "114") (pinfunction "MICIN1N_114") (pintype "passive+no_connect"))
    )
    (net (code "82") (name "unconnected-(U1-MICIN1P-Pad113)") (class "Default")
      (node (ref "U1") (pin "113") (pinfunction "MICIN1P_113") (pintype "passive+no_connect"))
    )
    (net (code "83") (name "unconnected-(U1-PC0{slash}SDC2_CLK{slash}SPI_MISO-Pad52)") (class "Default")
      (node (ref "U1") (pin "52") (pinfunction "PC0/SDC2_CLK/SPI_MISO_52") (pintype "passive+no_connect"))
    )
    (net (code "84") (name "unconnected-(U1-PE0{slash}CSI_PCLK{slash}LCD_CLK-Pad37)") (class "Default")
      (node (ref "U1") (pin "37") (pinfunction "PE0/CSI_PCLK/LCD_CLK_37") (pintype "passive+no_connect"))
    )
    (net (code "85") (name "unconnected-(U1-PE1{slash}CSI_MCLK{slash}LCD_DE-Pad36)") (class "Default")
      (node (ref "U1") (pin "36") (pinfunction "PE1/CSI_MCLK/LCD_DE_36") (pintype "passive+no_connect"))
    )
    (net (code "86") (name "unconnected-(U1-PE2{slash}CSI_HSYNC{slash}LCD_HSYNC-Pad35)") (class "Default")
      (node (ref "U1") (pin "35") (pinfunction "PE2/CSI_HSYNC/LCD_HSYNC_35") (pintype "passive+no_connect"))
    )
    (net (code "87") (name "unconnected-(U1-PE3{slash}CSI_VSYNC{slash}LCD_VSYNC-Pad34)") (class "Default")
      (node (ref "U1") (pin "34") (pinfunction "PE3/CSI_VSYNC/LCD_VSYNC_34") (pintype "passive+no_connect"))
    )
    (net (code "88") (name "unconnected-(U1-PE4{slash}CSI_D0{slash}LCD_D2-Pad33)") (class "Default")
      (node (ref "U1") (pin "33") (pinfunction "PE4/CSI_D0/LCD_D2_33") (pintype "passive+no_connect"))
    )
    (net (code "89") (name "unconnected-(U1-PE5{slash}CSI_D1{slash}LCD_D3-Pad32)") (class "Default")
      (node (ref "U1") (pin "32") (pinfunction "PE5/CSI_D1/LCD_D3_32") (pintype "passive+no_connect"))
    )
    (net (code "90") (name "unconnected-(U1-PE6{slash}CSI_D2{slash}LCD_D4-Pad31)") (class "Default")
      (node (ref "U1") (pin "31") (pinfunction "PE6/CSI_D2/LCD_D4_31") (pintype "passive+no_connect"))
    )
    (net (code "91") (name "unconnected-(U1-PE10{slash}CSI_D6{slash}LCD_D10-Pad24)") (class "Default")
      (node (ref "U1") (pin "24") (pinfunction "PE10/CSI_D6/LCD_D10_24") (pintype "passive+no_connect"))
    )
    (net (code "92") (name "unconnected-(U1-PE11{slash}CSI_D7{slash}LCD_D11-Pad23)") (class "Default")
      (node (ref "U1") (pin "23") (pinfunction "PE11/CSI_D7/LCD_D11_23") (pintype "passive+no_connect"))
    )
    (net (code "93") (name "unconnected-(U1-PE12{slash}CSI_D8{slash}LCD_D12-Pad22)") (class "Default")
      (node (ref "U1") (pin "22") (pinfunction "PE12/CSI_D8/LCD_D12_22") (pintype "passive+no_connect"))
    )
    (net (code "94") (name "unconnected-(U1-PE13{slash}CSI_D9{slash}LCD_D13-Pad18)") (class "Default")
      (node (ref "U1") (pin "18") (pinfunction "PE13/CSI_D9/LCD_D13_18") (pintype "passive+no_connect"))
    )
    (net (code "95") (name "unconnected-(U1-PE14{slash}CSI_D10{slash}LCD_D14-Pad17)") (class "Default")
      (node (ref "U1") (pin "17") (pinfunction "PE14/CSI_D10/LCD_D14_17") (pintype "passive+no_connect"))
    )
    (net (code "96") (name "unconnected-(U1-PE15{slash}CSI_D11{slash}LCD_D15-Pad16)") (class "Default")
      (node (ref "U1") (pin "16") (pinfunction "PE15/CSI_D11/LCD_D15_16") (pintype "passive+no_connect"))
    )
    (net (code "97") (name "unconnected-(U1-PE16{slash}CSI_D12{slash}LCD_D18-Pad15)") (class "Default")
      (node (ref "U1") (pin "15") (pinfunction "PE16/CSI_D12/LCD_D18_15") (pintype "passive+no_connect"))
    )
    (net (code "98") (name "unconnected-(U1-PE17{slash}CSI_D13{slash}LCD_D19-Pad14)") (class "Default")
      (node (ref "U1") (pin "14") (pinfunction "PE17/CSI_D13/LCD_D19_14") (pintype "passive+no_connect"))
    )
    (net (code "99") (name "unconnected-(U1-PE18{slash}CSI_D14{slash}LCD_D20-Pad13)") (class "Default")
      (node (ref "U1") (pin "13") (pinfunction "PE18/CSI_D14/LCD_D20_13") (pintype "passive+no_connect"))
    )
    (net (code "100") (name "unconnected-(U1-PE19{slash}CSI_D15{slash}LCD_D21-Pad11)") (class "Default")
      (node (ref "U1") (pin "11") (pinfunction "PE19/CSI_D15/LCD_D21_11") (pintype "passive+no_connect"))
    )
    (net (code "101") (name "unconnected-(U1-PE20{slash}CSI_FIELD{slash}CSI_MIPI_MCLK-Pad10)") (class "Default")
      (node (ref "U1") (pin "10") (pinfunction "PE20/CSI_FIELD/CSI_MIPI_MCLK_10") (pintype "passive+no_connect"))
    )
    (net (code "102") (name "unconnected-(U1-PE21{slash}CSI_SCK{slash}TWI1_SCK{slash}UART1_TX-Pad9)") (class "Default")
      (node (ref "U1") (pin "9") (pinfunction "PE21/CSI_SCK/TWI1_SCK/UART1_TX_9") (pintype "passive+no_connect"))
    )
    (net (code "103") (name "unconnected-(U1-PE22{slash}CSI_SDA{slash}TWI1_SDA{slash}UART1_RX-Pad8)") (class "Default")
      (node (ref "U1") (pin "8") (pinfunction "PE22/CSI_SDA/TWI1_SDA/UART1_RX_8") (pintype "passive+no_connect"))
    )
    (net (code "104") (name "unconnected-(U1-PE23{slash}LCD_D22-Pad7)") (class "Default")
      (node (ref "U1") (pin "7") (pinfunction "PE23/LCD_D22_7") (pintype "passive+no_connect"))
    )
    (net (code "105") (name "unconnected-(U1-PE24{slash}LCD_D23-Pad6)") (class "Default")
      (node (ref "U1") (pin "6") (pinfunction "PE24/LCD_D23_6") (pintype "passive+no_connect"))
    )
    (net (code "106") (name "unconnected-(U1-PF6-Pad100)") (class "Default")
      (node (ref "U1") (pin "100") (pinfunction "PF6_100") (pintype "passive+no_connect"))
    )
  )
)
